# motor_channel_x2.net
KiCad netlist of a schematic drawn in Altium Designer
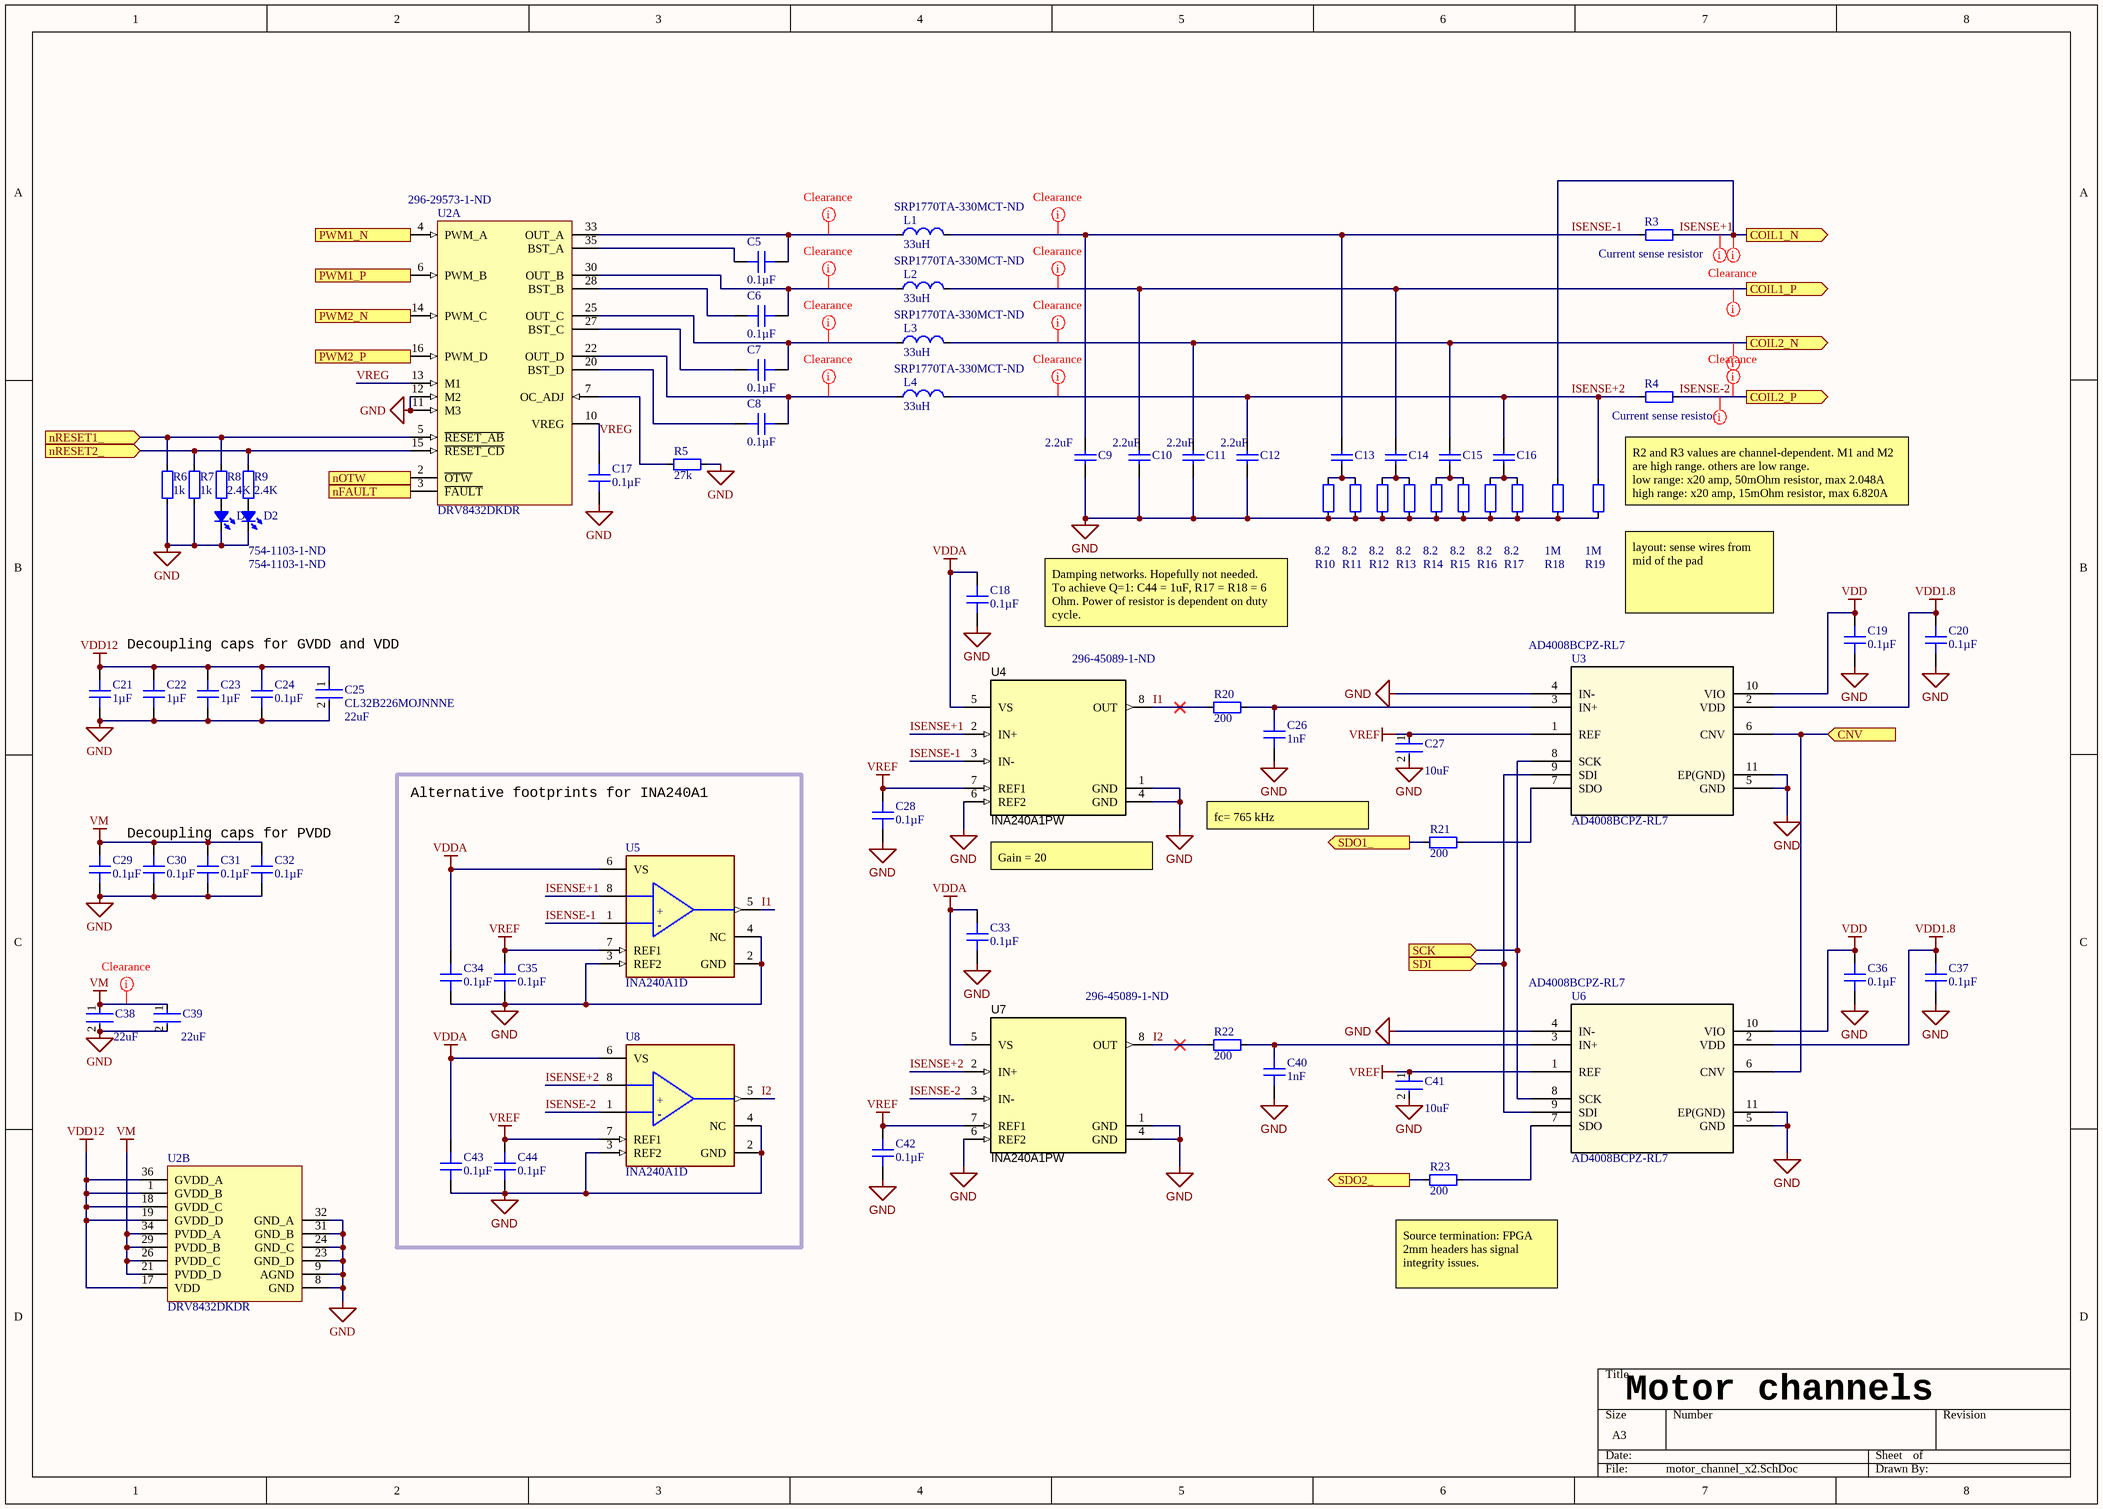
[diagram p0: motor_channel_x2.SchDoc]

(export (version "E")
  (design (tool "Eeschema 10.0.6"))
  (components
    (comp (ref "C5")
      (value "0.1µF")
      (footprint "FP-GRM188-0_1-e0_2_0_55-IPC_B")
      (description "CAP CER 0.1UF 100V X7R 0603")
      (fields (field (name "PART NUMBER") "06031C104KAT2A") (field (name "MANUFACTURER") "AVX Corporation"))
      (libsource (lib "Celestial Altium Library - altium_library") (part "Capacitor"))
    )
    (comp (ref "C6")
      (value "0.1µF")
      (footprint "FP-GRM188-0_1-e0_2_0_55-IPC_B")
      (description "CAP CER 0.1UF 100V X7R 0603")
      (fields (field (name "PART NUMBER") "06031C104KAT2A") (field (name "MANUFACTURER") "AVX Corporation"))
      (libsource (lib "Celestial Altium Library - altium_library") (part "Capacitor"))
    )
    (comp (ref "C7")
      (value "0.1µF")
      (footprint "FP-GRM188-0_1-e0_2_0_55-IPC_B")
      (description "CAP CER 0.1UF 100V X7R 0603")
      (fields (field (name "PART NUMBER") "06031C104KAT2A") (field (name "MANUFACTURER") "AVX Corporation"))
      (libsource (lib "Celestial Altium Library - altium_library") (part "Capacitor"))
    )
    (comp (ref "C8")
      (value "0.1µF")
      (footprint "FP-GRM188-0_1-e0_2_0_55-IPC_B")
      (description "CAP CER 0.1UF 100V X7R 0603")
      (fields (field (name "PART NUMBER") "06031C104KAT2A") (field (name "MANUFACTURER") "AVX Corporation"))
      (libsource (lib "Celestial Altium Library - altium_library") (part "Capacitor"))
    )
    (comp (ref "C9")
      (value "12061C225KAT2A")
      (footprint "CAPC3216X180X50NL20T25")
      (description "Chip Capacitor, 2.2 uF, +/- 10%, 100 V, -55 to 125 degC, 1206 (3216 Metric), RoHS, Tape and Reel")
      (fields
        (field (name "TOLERANCE") "10%")
        (field (name "VOLTAGE") "100V")
        (field (name "CAPACITANCE") "2.2uF")
      )
      (libsource (lib "Altium Content Vault") (part "CAP-NP-2"))
    )
    (comp (ref "C10")
      (value "12061C225KAT2A")
      (footprint "CAPC3216X180X50NL20T25")
      (description "Chip Capacitor, 2.2 uF, +/- 10%, 100 V, -55 to 125 degC, 1206 (3216 Metric), RoHS, Tape and Reel")
      (fields
        (field (name "TOLERANCE") "10%")
        (field (name "VOLTAGE") "100V")
        (field (name "CAPACITANCE") "2.2uF")
      )
      (libsource (lib "Altium Content Vault") (part "CAP-NP-2"))
    )
    (comp (ref "C11")
      (value "12061C225KAT2A")
      (footprint "CAPC3216X180X50NL20T25")
      (description "Chip Capacitor, 2.2 uF, +/- 10%, 100 V, -55 to 125 degC, 1206 (3216 Metric), RoHS, Tape and Reel")
      (fields
        (field (name "TOLERANCE") "10%")
        (field (name "VOLTAGE") "100V")
        (field (name "CAPACITANCE") "2.2uF")
      )
      (libsource (lib "Altium Content Vault") (part "CAP-NP-2"))
    )
    (comp (ref "C12")
      (value "12061C225KAT2A")
      (footprint "CAPC3216X180X50NL20T25")
      (description "Chip Capacitor, 2.2 uF, +/- 10%, 100 V, -55 to 125 degC, 1206 (3216 Metric), RoHS, Tape and Reel")
      (fields
        (field (name "TOLERANCE") "10%")
        (field (name "VOLTAGE") "100V")
        (field (name "CAPACITANCE") "2.2uF")
      )
      (libsource (lib "Altium Content Vault") (part "CAP-NP-2"))
    )
    (comp (ref "C13")
      (value "12061C105KAT2A")
      (footprint "CAPC3216X180X50NL20T25")
      (description "Chip Capacitor, 1 uF, +/- 10%, 100 V, -55 to 125 degC, 1206 (3216 Metric), RoHS, Tape and Reel")
      (fields (field (name "MANUFACTURER") "AVX"))
      (libsource (lib "Altium Content Vault") (part "CAP-NP-2"))
    )
    (comp (ref "C14")
      (value "12061C105KAT2A")
      (footprint "CAPC3216X180X50NL20T25")
      (description "Chip Capacitor, 1 uF, +/- 10%, 100 V, -55 to 125 degC, 1206 (3216 Metric), RoHS, Tape and Reel")
      (fields (field (name "MANUFACTURER") "AVX"))
      (libsource (lib "Altium Content Vault") (part "CAP-NP-2"))
    )
    (comp (ref "C15")
      (value "12061C105KAT2A")
      (footprint "CAPC3216X180X50NL20T25")
      (description "Chip Capacitor, 1 uF, +/- 10%, 100 V, -55 to 125 degC, 1206 (3216 Metric), RoHS, Tape and Reel")
      (fields (field (name "MANUFACTURER") "AVX"))
      (libsource (lib "Altium Content Vault") (part "CAP-NP-2"))
    )
    (comp (ref "C16")
      (value "12061C105KAT2A")
      (footprint "CAPC3216X180X50NL20T25")
      (description "Chip Capacitor, 1 uF, +/- 10%, 100 V, -55 to 125 degC, 1206 (3216 Metric), RoHS, Tape and Reel")
      (fields (field (name "MANUFACTURER") "AVX"))
      (libsource (lib "Altium Content Vault") (part "CAP-NP-2"))
    )
    (comp (ref "C17")
      (value "0.1µF")
      (footprint "FP-GRM155-0_05-IPC_B")
      (description "CAP CER 0.1UF 25V X7R 0402")
      (fields (field (name "PART NUMBER") "04023C104KAT2A") (field (name "MANUFACTURER") "AVX Corporation"))
      (libsource (lib "Celestial Altium Library - altium_library") (part "Capacitor"))
    )
    (comp (ref "C18")
      (value "0.1µF")
      (footprint "FP-GRM155-0_05-IPC_B")
      (description "CAP CER 0.1UF 25V X7R 0402")
      (fields (field (name "MANUFACTURER") "AVX Corporation") (field (name "PART NUMBER") "04023C104KAT2A"))
      (libsource (lib "Celestial Altium Library - altium_library") (part "Capacitor"))
    )
    (comp (ref "C19")
      (value "0.1µF")
      (footprint "FP-GRM155-0_05-IPC_B")
      (description "CAP CER 0.1UF 25V X7R 0402")
      (fields (field (name "MANUFACTURER") "AVX Corporation") (field (name "PART NUMBER") "04023C104KAT2A"))
      (libsource (lib "Celestial Altium Library - altium_library") (part "Capacitor"))
    )
    (comp (ref "C20")
      (value "0.1µF")
      (footprint "FP-GRM155-0_05-IPC_B")
      (description "CAP CER 0.1UF 25V X7R 0402")
      (fields (field (name "MANUFACTURER") "AVX Corporation") (field (name "PART NUMBER") "04023C104KAT2A"))
      (libsource (lib "Celestial Altium Library - altium_library") (part "Capacitor"))
    )
    (comp (ref "C21")
      (value "1µF")
      (footprint "FP-GRM188-0_1-e0_2_0_55-IPC_B")
      (description "CAP CER 1UF 25V X7R 0603")
      (fields (field (name "PART NUMBER") "TMK107B7105KA-T") (field (name "MANUFACTURER") "Taiyo Yuden"))
      (libsource (lib "Celestial Altium Library - altium_library") (part "Capacitor"))
    )
    (comp (ref "C22")
      (value "1µF")
      (footprint "FP-GRM188-0_1-e0_2_0_55-IPC_B")
      (description "CAP CER 1UF 25V X7R 0603")
      (fields (field (name "PART NUMBER") "TMK107B7105KA-T") (field (name "MANUFACTURER") "Taiyo Yuden"))
      (libsource (lib "Celestial Altium Library - altium_library") (part "Capacitor"))
    )
    (comp (ref "C23")
      (value "1µF")
      (footprint "FP-GRM188-0_1-e0_2_0_55-IPC_B")
      (description "CAP CER 1UF 25V X7R 0603")
      (fields (field (name "PART NUMBER") "TMK107B7105KA-T") (field (name "MANUFACTURER") "Taiyo Yuden"))
      (libsource (lib "Celestial Altium Library - altium_library") (part "Capacitor"))
    )
    (comp (ref "C24")
      (value "0.1µF")
      (footprint "FP-GRM155-0_05-IPC_B")
      (description "CAP CER 0.1UF 25V X7R 0402")
      (fields (field (name "MANUFACTURER") "AVX Corporation") (field (name "PART NUMBER") "04023C104KAT2A"))
      (libsource (lib "Celestial Altium Library - altium_library") (part "Capacitor"))
    )
    (comp (ref "C25")
      (value "CL32B226MOJNNNE")
      (footprint "FP-CL32-IPC_B")
      (description "Cap Ceramic 22uF 16V X7R ±20% SMD 1210 +125°C Embossed T/R")
      (fields (field (name "CAPACITANCE") "22uF") (field (name "TOLERANCE") "20%"))
      (libsource (lib "Altium Content Vault") (part "b4654b650e69147ec39a6b967a45e02"))
    )
    (comp (ref "C26")
      (value "1nF")
      (footprint "FP-GRM155-0_05-IPC_B")
      (description "CAP CER 1000PF 25V X7R 0402")
      (fields (field (name "MANUFACTURER") "AVX Corporation") (field (name "PART NUMBER") "04023C102KAT2A"))
      (libsource (lib "Celestial Altium Library - altium_library") (part "Capacitor"))
    )
    (comp (ref "C27")
      (value "CL21B106KQQNNNG")
      (footprint "FP-CL21-IPC_C")
      (description "CL21 Series 0805 10uF 6.3V ±10% Tolerance X7R Multilayer Ceramic Chip Capacitor")
      (fields
        (field (name "CAPACITANCE") "10uF")
        (field (name "TOLERANCE") "10%")
        (field (name "VOLTAGE") "6.3V")
      )
      (libsource (lib "Altium Content Vault") (part "b4654b650e69147ec39a6b967a45e02"))
    )
    (comp (ref "C28")
      (value "0.1µF")
      (footprint "FP-GRM155-0_05-IPC_B")
      (description "CAP CER 0.1UF 25V X7R 0402")
      (fields (field (name "MANUFACTURER") "AVX Corporation") (field (name "PART NUMBER") "04023C104KAT2A"))
      (libsource (lib "Celestial Altium Library - altium_library") (part "Capacitor"))
    )
    (comp (ref "C29")
      (value "0.1µF")
      (footprint "FP-GRM188-0_1-e0_2_0_55-IPC_B")
      (description "CAP CER 0.1UF 100V X7R 0603")
      (fields (field (name "PART NUMBER") "06031C104KAT2A") (field (name "MANUFACTURER") "AVX Corporation"))
      (libsource (lib "Celestial Altium Library - altium_library") (part "Capacitor"))
    )
    (comp (ref "C30")
      (value "0.1µF")
      (footprint "FP-GRM188-0_1-e0_2_0_55-IPC_B")
      (description "CAP CER 0.1UF 100V X7R 0603")
      (fields (field (name "PART NUMBER") "06031C104KAT2A") (field (name "MANUFACTURER") "AVX Corporation"))
      (libsource (lib "Celestial Altium Library - altium_library") (part "Capacitor"))
    )
    (comp (ref "C31")
      (value "0.1µF")
      (footprint "FP-GRM188-0_1-e0_2_0_55-IPC_B")
      (description "CAP CER 0.1UF 100V X7R 0603")
      (fields (field (name "PART NUMBER") "06031C104KAT2A") (field (name "MANUFACTURER") "AVX Corporation"))
      (libsource (lib "Celestial Altium Library - altium_library") (part "Capacitor"))
    )
    (comp (ref "C32")
      (value "0.1µF")
      (footprint "FP-GRM188-0_1-e0_2_0_55-IPC_B")
      (description "CAP CER 0.1UF 100V X7R 0603")
      (fields (field (name "PART NUMBER") "06031C104KAT2A") (field (name "MANUFACTURER") "AVX Corporation"))
      (libsource (lib "Celestial Altium Library - altium_library") (part "Capacitor"))
    )
    (comp (ref "C33")
      (value "0.1µF")
      (footprint "FP-GRM155-0_05-IPC_B")
      (description "CAP CER 0.1UF 25V X7R 0402")
      (fields (field (name "MANUFACTURER") "AVX Corporation") (field (name "PART NUMBER") "04023C104KAT2A"))
      (libsource (lib "Celestial Altium Library - altium_library") (part "Capacitor"))
    )
    (comp (ref "C34")
      (value "0.1µF")
      (footprint "FP-GRM155-0_05-IPC_B")
      (description "CAP CER 0.1UF 25V X7R 0402")
      (fields (field (name "MANUFACTURER") "AVX Corporation") (field (name "PART NUMBER") "04023C104KAT2A"))
      (libsource (lib "Celestial Altium Library - altium_library") (part "Capacitor"))
    )
    (comp (ref "C35")
      (value "0.1µF")
      (footprint "FP-GRM155-0_05-IPC_B")
      (description "CAP CER 0.1UF 25V X7R 0402")
      (fields (field (name "MANUFACTURER") "AVX Corporation") (field (name "PART NUMBER") "04023C104KAT2A"))
      (libsource (lib "Celestial Altium Library - altium_library") (part "Capacitor"))
    )
    (comp (ref "C36")
      (value "0.1µF")
      (footprint "FP-GRM155-0_05-IPC_B")
      (description "CAP CER 0.1UF 25V X7R 0402")
      (fields (field (name "MANUFACTURER") "AVX Corporation") (field (name "PART NUMBER") "04023C104KAT2A"))
      (libsource (lib "Celestial Altium Library - altium_library") (part "Capacitor"))
    )
    (comp (ref "C37")
      (value "0.1µF")
      (footprint "FP-GRM155-0_05-IPC_B")
      (description "CAP CER 0.1UF 25V X7R 0402")
      (fields (field (name "MANUFACTURER") "AVX Corporation") (field (name "PART NUMBER") "04023C104KAT2A"))
      (libsource (lib "Celestial Altium Library - altium_library") (part "Capacitor"))
    )
    (comp (ref "C38")
      (value "KRM55WR72A226MH01L")
      (footprint "FP-KRM55W-6_1_5_3_6_7_1_2-MFG")
      (description "CAP CER 22UF 100V X7R SMD")
      (fields (field (name "CAPACITANCE") "22uF") (field (name "TOLERANCE") "20%"))
      (libsource (lib "Altium Content Vault") (part "02cd4be3c70576c341d710602a673aa"))
    )
    (comp (ref "C39")
      (value "KRM55WR72A226MH01L")
      (footprint "FP-KRM55W-6_1_5_3_6_7_1_2-MFG")
      (description "CAP CER 22UF 100V X7R SMD")
      (fields (field (name "CAPACITANCE") "22uF") (field (name "TOLERANCE") "20%"))
      (libsource (lib "Altium Content Vault") (part "02cd4be3c70576c341d710602a673aa"))
    )
    (comp (ref "C40")
      (value "1nF")
      (footprint "FP-GRM155-0_05-IPC_B")
      (description "CAP CER 1000PF 25V X7R 0402")
      (fields (field (name "MANUFACTURER") "AVX Corporation") (field (name "PART NUMBER") "04023C102KAT2A"))
      (libsource (lib "Celestial Altium Library - altium_library") (part "Capacitor"))
    )
    (comp (ref "C41")
      (value "CL21B106KQQNNNG")
      (footprint "FP-CL21-IPC_C")
      (description "CL21 Series 0805 10uF 6.3V ±10% Tolerance X7R Multilayer Ceramic Chip Capacitor")
      (fields
        (field (name "CAPACITANCE") "10uF")
        (field (name "TOLERANCE") "10%")
        (field (name "VOLTAGE") "6.3V")
      )
      (libsource (lib "Altium Content Vault") (part "b4654b650e69147ec39a6b967a45e02"))
    )
    (comp (ref "C42")
      (value "0.1µF")
      (footprint "FP-GRM155-0_05-IPC_B")
      (description "CAP CER 0.1UF 25V X7R 0402")
      (fields (field (name "MANUFACTURER") "AVX Corporation") (field (name "PART NUMBER") "04023C104KAT2A"))
      (libsource (lib "Celestial Altium Library - altium_library") (part "Capacitor"))
    )
    (comp (ref "C43")
      (value "0.1µF")
      (footprint "FP-GRM155-0_05-IPC_B")
      (description "CAP CER 0.1UF 25V X7R 0402")
      (fields (field (name "MANUFACTURER") "AVX Corporation") (field (name "PART NUMBER") "04023C104KAT2A"))
      (libsource (lib "Celestial Altium Library - altium_library") (part "Capacitor"))
    )
    (comp (ref "C44")
      (value "0.1µF")
      (footprint "FP-GRM155-0_05-IPC_B")
      (description "CAP CER 0.1UF 25V X7R 0402")
      (fields (field (name "MANUFACTURER") "AVX Corporation") (field (name "PART NUMBER") "04023C104KAT2A"))
      (libsource (lib "Celestial Altium Library - altium_library") (part "Capacitor"))
    )
    (comp (ref "D1")
      (value "LED_0402")
      (footprint "Components - 10.02.21 - 05.05:ROHM-SML-P11MT_V")
      (description "LED ORANGE CLEAR CHIP SMD")
      (fields
        (field (name "SUPPLIER PART NUMBER 1") "754-1103-1-ND")
        (field (name "MANUFACTURER") "Kingbright")
        (field (name "MANUFACTURER PART NUMBER") "APHHS1005SECK")
      )
      (libsource (lib "SCH_Active") (part "LED_0402"))
    )
    (comp (ref "D2")
      (value "LED_0402")
      (footprint "Components - 10.02.21 - 05.05:ROHM-SML-P11MT_V")
      (description "LED ORANGE CLEAR CHIP SMD")
      (fields
        (field (name "SUPPLIER PART NUMBER 1") "754-1103-1-ND")
        (field (name "MANUFACTURER") "Kingbright")
        (field (name "MANUFACTURER PART NUMBER") "APHHS1005SECK")
      )
      (libsource (lib "SCH_Active") (part "LED_0402"))
    )
    (comp (ref "L1")
      (value "33uH")
      (footprint "SRP1770TA")
      (fields
        (field (name "MANUFACTURER") "TDK")
        (field (name "MANUFACTURER PART NUMBER") "MPZ2012S300AT000")
        (field (name "TOLERANCE") "20%")
        (field (name "SUPPLIER PART NUMBER 1") "SRP1770TA-330MCT-ND")
      )
      (libsource (lib "SCH_Passive") (part "Ind_0805"))
    )
    (comp (ref "L2")
      (value "33uH")
      (footprint "SRP1770TA")
      (fields
        (field (name "MANUFACTURER") "TDK")
        (field (name "MANUFACTURER PART NUMBER") "MPZ2012S300AT000")
        (field (name "TOLERANCE") "20%")
        (field (name "SUPPLIER PART NUMBER 1") "SRP1770TA-330MCT-ND")
      )
      (libsource (lib "SCH_Passive") (part "Ind_0805"))
    )
    (comp (ref "L3")
      (value "33uH")
      (footprint "SRP1770TA")
      (fields
        (field (name "MANUFACTURER") "TDK")
        (field (name "MANUFACTURER PART NUMBER") "MPZ2012S300AT000")
        (field (name "TOLERANCE") "20%")
        (field (name "SUPPLIER PART NUMBER 1") "SRP1770TA-330MCT-ND")
      )
      (libsource (lib "SCH_Passive") (part "Ind_0805"))
    )
    (comp (ref "L4")
      (value "33uH")
      (footprint "SRP1770TA")
      (fields
        (field (name "MANUFACTURER") "TDK")
        (field (name "MANUFACTURER PART NUMBER") "MPZ2012S300AT000")
        (field (name "TOLERANCE") "20%")
        (field (name "SUPPLIER PART NUMBER 1") "SRP1770TA-330MCT-ND")
      )
      (libsource (lib "SCH_Passive") (part "Ind_0805"))
    )
    (comp (ref "R3")
      (value "Current sense resistor")
      (footprint "STACKPOLE CSR2512")
      (description "RES 2512")
      (libsource (lib "dvrk-s-pwm_2") (part "Res_0402_3"))
    )
    (comp (ref "R4")
      (value "Current sense resistor")
      (footprint "STACKPOLE CSR2512")
      (description "RES 2512")
      (libsource (lib "dvrk-s-pwm_2") (part "Res_0402_3"))
    )
    (comp (ref "R5")
      (value "27k")
      (footprint "FP-CRCW0402-e3-IPC_B")
      (description "Resistor")
      (fields (field (name "Comment") "Res_0402"))
      (libsource (lib "SCH_Passive") (part "Res_0402"))
    )
    (comp (ref "R6")
      (value "1k")
      (footprint "FP-CRCW0805-HPe3-IPC_B")
      (description "Resistor")
      (fields (field (name "Comment") "Res_0805"))
      (libsource (lib "SCH_Passive") (part "Res_0805"))
    )
    (comp (ref "R7")
      (value "1k")
      (footprint "FP-CRCW0805-HPe3-IPC_B")
      (description "Resistor")
      (fields (field (name "Comment") "Res_0805"))
      (libsource (lib "SCH_Passive") (part "Res_0805"))
    )
    (comp (ref "R8")
      (value "2.4K")
      (footprint "FP-CRCW0402-e3-IPC_B")
      (description "Resistor")
      (fields (field (name "Comment") "Res_0402"))
      (libsource (lib "") (part "Res_0402_1"))
    )
    (comp (ref "R9")
      (value "2.4K")
      (footprint "FP-CRCW0402-e3-IPC_B")
      (description "Resistor")
      (fields (field (name "Comment") "Res_0402"))
      (libsource (lib "") (part "Res_0402_1"))
    )
    (comp (ref "R10")
      (value "8.2")
      (footprint "RESC3216X70X50NL05T20")
      (description "Resistor")
      (fields (field (name "Comment") "Res_0402"))
      (libsource (lib "") (part "Res_0402_1"))
    )
    (comp (ref "R11")
      (value "8.2")
      (footprint "RESC3216X70X50NL05T20")
      (description "Resistor")
      (fields (field (name "Comment") "Res_0402"))
      (libsource (lib "") (part "Res_0402_1"))
    )
    (comp (ref "R12")
      (value "8.2")
      (footprint "RESC3216X70X50NL05T20")
      (description "Resistor")
      (fields (field (name "Comment") "Res_0402"))
      (libsource (lib "") (part "Res_0402_1"))
    )
    (comp (ref "R13")
      (value "8.2")
      (footprint "RESC3216X70X50NL05T20")
      (description "Resistor")
      (fields (field (name "Comment") "Res_0402"))
      (libsource (lib "") (part "Res_0402_1"))
    )
    (comp (ref "R14")
      (value "8.2")
      (footprint "RESC3216X70X50NL05T20")
      (description "Resistor")
      (fields (field (name "Comment") "Res_0402"))
      (libsource (lib "") (part "Res_0402_1"))
    )
    (comp (ref "R15")
      (value "8.2")
      (footprint "RESC3216X70X50NL05T20")
      (description "Resistor")
      (fields (field (name "Comment") "Res_0402"))
      (libsource (lib "") (part "Res_0402_1"))
    )
    (comp (ref "R16")
      (value "8.2")
      (footprint "RESC3216X70X50NL05T20")
      (description "Resistor")
      (fields (field (name "Comment") "Res_0402"))
      (libsource (lib "") (part "Res_0402_1"))
    )
    (comp (ref "R17")
      (value "8.2")
      (footprint "RESC3216X70X50NL05T20")
      (description "Resistor")
      (fields (field (name "Comment") "Res_0402"))
      (libsource (lib "") (part "Res_0402_1"))
    )
    (comp (ref "R18")
      (value "1M")
      (footprint "FP-CRCW0402-e3-IPC_B")
      (description "Resistor")
      (fields (field (name "Comment") "Res_0402"))
      (libsource (lib "") (part "Res_0402_1"))
    )
    (comp (ref "R19")
      (value "1M")
      (footprint "FP-CRCW0402-e3-IPC_B")
      (description "Resistor")
      (fields (field (name "Comment") "Res_0402"))
      (libsource (lib "") (part "Res_0402_1"))
    )
    (comp (ref "R20")
      (value "200")
      (footprint "FP-CRCW0402-e3-IPC_B")
      (description "Resistor")
      (fields (field (name "Comment") "Res_0402"))
      (libsource (lib "SCH_Passive") (part "Res_0402"))
    )
    (comp (ref "R21")
      (value "200")
      (footprint "FP-CRCW0402-e3-IPC_B")
      (description "Resistor")
      (fields (field (name "Comment") "Res_0402"))
      (libsource (lib "SCH_Passive") (part "Res_0402"))
    )
    (comp (ref "R22")
      (value "200")
      (footprint "FP-CRCW0402-e3-IPC_B")
      (description "Resistor")
      (fields (field (name "Comment") "Res_0402"))
      (libsource (lib "SCH_Passive") (part "Res_0402"))
    )
    (comp (ref "R23")
      (value "200")
      (footprint "FP-CRCW0402-e3-IPC_B")
      (description "Resistor")
      (fields (field (name "Comment") "Res_0402"))
      (libsource (lib "SCH_Passive") (part "Res_0402"))
    )
    (comp (ref "U2")
      (value "DRV8432DKDR")
      (footprint "DKD0036A_L_extra_clearance")
      (fields
        (field (name "SUPPLIER PART NUMBER 1") "296-29573-1-ND")
        (field (name "MANUFACTURER") "Texas Instruments")
      )
      (libsource (lib "dvrk-s-pwm_2") (part "TI-DRV8432DKD36"))
    )
    (comp (ref "U3")
      (value "AD4008BCPZ-RL7")
      (footprint "CP_10_9")
      (description "16-Bit, 2 MSPS/1 MSPS/500 kSPS,\r\nPrecision, Pseudo Differential, SAR ADCs")
      (fields (field (name "SUPPLIER PART NUMBER 1") "AD4008BCPZ-RL7"))
      (libsource (lib "dvrk-s-pwm") (part "AD4008BCPZ-RL7"))
    )
    (comp (ref "U4")
      (value "INA240A1PW")
      (footprint "drac_v31:PW0008A_N")
      (description "TEXAS INSTRUMENTS - INA240A1PWR . - CURRENT SENSE AMPLIFIER, 400KHZ, TSSOP-8")
      (fields
        (field (name "MANUFACTURER") "Texas Instruments")
        (field (name "MANUFACTURER PART NUMBER") "INA240A1PWR")
        (field (name "SUPPLIER PART NUMBER 1") "296-45089-1-ND")
        (field (name "SYMBOLCREATOR") "Altium")
        (field (name "PUBLISHER") "Texas Instruments")
      )
      (libsource (lib "TI_Pre_RTM") (part "INA240A1PW"))
    )
    (comp (ref "U5")
      (value "INA240A1D")
      (footprint "drac_v31:FP-D0008A-IPC_C")
      (description "IC CURR SENSE 1 CIRCUIT 8SOIC")
      (libsource (lib "dvrk-s-pwm_2") (part "9e341c39a96748c47c80be35c7bc850"))
    )
    (comp (ref "U6")
      (value "AD4008BCPZ-RL7")
      (footprint "CP_10_9")
      (description "16-Bit, 2 MSPS/1 MSPS/500 kSPS,\r\nPrecision, Pseudo Differential, SAR ADCs")
      (fields (field (name "SUPPLIER PART NUMBER 1") "AD4008BCPZ-RL7"))
      (libsource (lib "dvrk-s-pwm") (part "AD4008BCPZ-RL7"))
    )
    (comp (ref "U7")
      (value "INA240A1PW")
      (footprint "drac_v31:PW0008A_N")
      (description "TEXAS INSTRUMENTS - INA240A1PWR . - CURRENT SENSE AMPLIFIER, 400KHZ, TSSOP-8")
      (fields
        (field (name "MANUFACTURER") "Texas Instruments")
        (field (name "MANUFACTURER PART NUMBER") "INA240A1PWR")
        (field (name "SUPPLIER PART NUMBER 1") "296-45089-1-ND")
        (field (name "SYMBOLCREATOR") "Altium")
        (field (name "PUBLISHER") "Texas Instruments")
      )
      (libsource (lib "TI_Pre_RTM") (part "INA240A1PW"))
    )
    (comp (ref "U8")
      (value "INA240A1D")
      (footprint "drac_v31:FP-D0008A-IPC_C")
      (description "IC CURR SENSE 1 CIRCUIT 8SOIC")
      (libsource (lib "dvrk-s-pwm_2") (part "9e341c39a96748c47c80be35c7bc850"))
    )
  )
  (nets
    (net (code "1") (name "/CNV") (class "Default")
      (node (ref "U3") (pin "6") (pinfunction "CNV_6") (pintype "passive"))
      (node (ref "U6") (pin "6") (pinfunction "CNV_6") (pintype "passive"))
    )
    (net (code "2") (name "/COIL1_P") (class "Default")
      (node (ref "C10") (pin "2") (pinfunction "2_2") (pintype "passive"))
      (node (ref "C14") (pin "1") (pinfunction "1_1") (pintype "passive"))
      (node (ref "L2") (pin "2") (pinfunction "2_2") (pintype "passive"))
    )
    (net (code "3") (name "/COIL2_N") (class "Default")
      (node (ref "C11") (pin "2") (pinfunction "2_2") (pintype "passive"))
      (node (ref "C15") (pin "1") (pinfunction "1_1") (pintype "passive"))
      (node (ref "L3") (pin "2") (pinfunction "2_2") (pintype "passive"))
    )
    (net (code "4") (name "/I1") (class "Default")
      (node (ref "R20") (pin "1") (pinfunction "1_1") (pintype "passive"))
      (node (ref "U4") (pin "8") (pinfunction "OUT_8") (pintype "output"))
      (node (ref "U5") (pin "5") (pinfunction "OUT_5") (pintype "output"))
    )
    (net (code "5") (name "/I2") (class "Default")
      (node (ref "R22") (pin "1") (pinfunction "1_1") (pintype "passive"))
      (node (ref "U7") (pin "8") (pinfunction "OUT_8") (pintype "output"))
      (node (ref "U8") (pin "5") (pinfunction "OUT_5") (pintype "output"))
    )
    (net (code "6") (name "/ISENSE+1") (class "Default")
      (node (ref "R18") (pin "2") (pinfunction "2_2") (pintype "passive"))
      (node (ref "R3") (pin "2") (pinfunction "2_2") (pintype "passive"))
      (node (ref "U4") (pin "2") (pinfunction "IN+_2") (pintype "input"))
      (node (ref "U5") (pin "8") (pinfunction "IN+_8") (pintype "tri_state"))
    )
    (net (code "7") (name "/ISENSE+2") (class "Default")
      (node (ref "C12") (pin "2") (pinfunction "2_2") (pintype "passive"))
      (node (ref "C16") (pin "1") (pinfunction "1_1") (pintype "passive"))
      (node (ref "L4") (pin "2") (pinfunction "2_2") (pintype "passive"))
      (node (ref "R19") (pin "2") (pinfunction "2_2") (pintype "passive"))
      (node (ref "R4") (pin "1") (pinfunction "1_1") (pintype "passive"))
      (node (ref "U7") (pin "2") (pinfunction "IN+_2") (pintype "input"))
      (node (ref "U8") (pin "8") (pinfunction "IN+_8") (pintype "tri_state"))
    )
    (net (code "8") (name "/ISENSE-1") (class "Default")
      (node (ref "C13") (pin "1") (pinfunction "1_1") (pintype "passive"))
      (node (ref "C9") (pin "2") (pinfunction "2_2") (pintype "passive"))
      (node (ref "L1") (pin "2") (pinfunction "2_2") (pintype "passive"))
      (node (ref "R3") (pin "1") (pinfunction "1_1") (pintype "passive"))
      (node (ref "U4") (pin "3") (pinfunction "IN-_3") (pintype "input"))
      (node (ref "U5") (pin "1") (pinfunction "IN-_1") (pintype "tri_state"))
    )
    (net (code "9") (name "/ISENSE-2") (class "Default")
      (node (ref "R4") (pin "2") (pinfunction "2_2") (pintype "passive"))
      (node (ref "U7") (pin "3") (pinfunction "IN-_3") (pintype "input"))
      (node (ref "U8") (pin "1") (pinfunction "IN-_1") (pintype "tri_state"))
    )
    (net (code "10") (name "/PWM1_N") (class "Default")
      (node (ref "U2") (pin "4") (pinfunction "PWM_A_4") (pintype "input"))
    )
    (net (code "11") (name "/PWM1_P") (class "Default")
      (node (ref "U2") (pin "6") (pinfunction "PWM_B_6") (pintype "input"))
    )
    (net (code "12") (name "/PWM2_N") (class "Default")
      (node (ref "U2") (pin "14") (pinfunction "PWM_C_14") (pintype "input"))
    )
    (net (code "13") (name "/PWM2_P") (class "Default")
      (node (ref "U2") (pin "16") (pinfunction "PWM_D_16") (pintype "input"))
    )
    (net (code "14") (name "/SCK") (class "Default")
      (node (ref "U3") (pin "8") (pinfunction "SCK_8") (pintype "passive"))
      (node (ref "U6") (pin "8") (pinfunction "SCK_8") (pintype "passive"))
    )
    (net (code "15") (name "/SDI") (class "Default")
      (node (ref "U3") (pin "9") (pinfunction "SDI_9") (pintype "passive"))
      (node (ref "U6") (pin "9") (pinfunction "SDI_9") (pintype "passive"))
    )
    (net (code "16") (name "/SDO1_") (class "Default")
      (node (ref "R21") (pin "1") (pinfunction "1_1") (pintype "passive"))
    )
    (net (code "17") (name "/SDO2_") (class "Default")
      (node (ref "R23") (pin "1") (pinfunction "1_1") (pintype "passive"))
    )
    (net (code "18") (name "/VREG") (class "Default")
      (node (ref "C17") (pin "1") (pinfunction "1_1") (pintype "passive"))
      (node (ref "U2") (pin "10") (pinfunction "VREG_10") (pintype "passive"))
      (node (ref "U2") (pin "13") (pinfunction "M1_13") (pintype "input"))
    )
    (net (code "19") (name "/nFAULT") (class "Default")
      (node (ref "U2") (pin "3") (pinfunction "~{FAULT}_3") (pintype "open_collector"))
    )
    (net (code "20") (name "/nOTW") (class "Default")
      (node (ref "U2") (pin "2") (pinfunction "~{OTW}_2") (pintype "open_collector"))
    )
    (net (code "21") (name "/nRESET1_") (class "Default")
      (node (ref "R6") (pin "2") (pinfunction "2_2") (pintype "passive"))
      (node (ref "R8") (pin "2") (pinfunction "2_2") (pintype "passive"))
      (node (ref "U2") (pin "5") (pinfunction "~{RESET_AB}_5") (pintype "input"))
    )
    (net (code "22") (name "/nRESET2_") (class "Default")
      (node (ref "R7") (pin "2") (pinfunction "2_2") (pintype "passive"))
      (node (ref "R9") (pin "2") (pinfunction "2_2") (pintype "passive"))
      (node (ref "U2") (pin "15") (pinfunction "~{RESET_CD}_15") (pintype "input"))
    )
    (net (code "23") (name "GND") (class "Default")
      (node (ref "C10") (pin "1") (pinfunction "1_1") (pintype "passive"))
      (node (ref "C11") (pin "1") (pinfunction "1_1") (pintype "passive"))
      (node (ref "C12") (pin "1") (pinfunction "1_1") (pintype "passive"))
      (node (ref "C17") (pin "2") (pinfunction "2_2") (pintype "passive"))
      (node (ref "C18") (pin "2") (pinfunction "2_2") (pintype "passive"))
      (node (ref "C19") (pin "2") (pinfunction "2_2") (pintype "passive"))
      (node (ref "C20") (pin "2") (pinfunction "2_2") (pintype "passive"))
      (node (ref "C21") (pin "2") (pinfunction "2_2") (pintype "passive"))
      (node (ref "C22") (pin "2") (pinfunction "2_2") (pintype "passive"))
      (node (ref "C23") (pin "2") (pinfunction "2_2") (pintype "passive"))
      (node (ref "C24") (pin "2") (pinfunction "2_2") (pintype "passive"))
      (node (ref "C25") (pin "2") (pinfunction "2_2") (pintype "passive"))
      (node (ref "C26") (pin "2") (pinfunction "2_2") (pintype "passive"))
      (node (ref "C27") (pin "2") (pinfunction "2_2") (pintype "passive"))
      (node (ref "C28") (pin "2") (pinfunction "2_2") (pintype "passive"))
      (node (ref "C29") (pin "2") (pinfunction "2_2") (pintype "passive"))
      (node (ref "C30") (pin "2") (pinfunction "2_2") (pintype "passive"))
      (node (ref "C31") (pin "2") (pinfunction "2_2") (pintype "passive"))
      (node (ref "C32") (pin "2") (pinfunction "2_2") (pintype "passive"))
      (node (ref "C33") (pin "2") (pinfunction "2_2") (pintype "passive"))
      (node (ref "C34") (pin "2") (pinfunction "2_2") (pintype "passive"))
      (node (ref "C35") (pin "2") (pinfunction "2_2") (pintype "passive"))
      (node (ref "C36") (pin "2") (pinfunction "2_2") (pintype "passive"))
      (node (ref "C37") (pin "2") (pinfunction "2_2") (pintype "passive"))
      (node (ref "C38") (pin "2") (pinfunction "2_2") (pintype "passive"))
      (node (ref "C39") (pin "2") (pinfunction "2_2") (pintype "passive"))
      (node (ref "C40") (pin "2") (pinfunction "2_2") (pintype "passive"))
      (node (ref "C41") (pin "2") (pinfunction "2_2") (pintype "passive"))
      (node (ref "C42") (pin "2") (pinfunction "2_2") (pintype "passive"))
      (node (ref "C43") (pin "2") (pinfunction "2_2") (pintype "passive"))
      (node (ref "C44") (pin "2") (pinfunction "2_2") (pintype "passive"))
      (node (ref "C9") (pin "1") (pinfunction "1_1") (pintype "passive"))
      (node (ref "D1") (pin "2") (pinfunction "K_2") (pintype "passive"))
      (node (ref "D2") (pin "2") (pinfunction "K_2") (pintype "passive"))
      (node (ref "R10") (pin "1") (pinfunction "1_1") (pintype "passive"))
      (node (ref "R11") (pin "1") (pinfunction "1_1") (pintype "passive"))
      (node (ref "R12") (pin "1") (pinfunction "1_1") (pintype "passive"))
      (node (ref "R13") (pin "1") (pinfunction "1_1") (pintype "passive"))
      (node (ref "R14") (pin "1") (pinfunction "1_1") (pintype "passive"))
      (node (ref "R15") (pin "1") (pinfunction "1_1") (pintype "passive"))
      (node (ref "R16") (pin "1") (pinfunction "1_1") (pintype "passive"))
      (node (ref "R17") (pin "1") (pinfunction "1_1") (pintype "passive"))
      (node (ref "R18") (pin "1") (pinfunction "1_1") (pintype "passive"))
      (node (ref "R19") (pin "1") (pinfunction "1_1") (pintype "passive"))
      (node (ref "R5") (pin "2") (pinfunction "2_2") (pintype "passive"))
      (node (ref "R6") (pin "1") (pinfunction "1_1") (pintype "passive"))
      (node (ref "R7") (pin "1") (pinfunction "1_1") (pintype "passive"))
      (node (ref "U2") (pin "11") (pinfunction "M3_11") (pintype "input"))
      (node (ref "U2") (pin "12") (pinfunction "M2_12") (pintype "input"))
      (node (ref "U2") (pin "23") (pinfunction "GND_D_23") (pintype "power_in"))
      (node (ref "U2") (pin "24") (pinfunction "GND_C_24") (pintype "power_in"))
      (node (ref "U2") (pin "31") (pinfunction "GND_B_31") (pintype "power_in"))
      (node (ref "U2") (pin "32") (pinfunction "GND_A_32") (pintype "power_in"))
      (node (ref "U2") (pin "8") (pinfunction "GND_8") (pintype "power_in"))
      (node (ref "U2") (pin "9") (pinfunction "AGND_9") (pintype "power_in"))
      (node (ref "U3") (pin "11") (pinfunction "EP(GND)_11") (pintype "passive"))
      (node (ref "U3") (pin "4") (pinfunction "IN-_4") (pintype "passive"))
      (node (ref "U3") (pin "5") (pinfunction "GND_5") (pintype "passive"))
      (node (ref "U4") (pin "1") (pinfunction "GND_1") (pintype "power_in"))
      (node (ref "U4") (pin "4") (pinfunction "GND_4") (pintype "power_in"))
      (node (ref "U4") (pin "6") (pinfunction "REF2_6") (pintype "input"))
      (node (ref "U5") (pin "2") (pinfunction "GND_2") (pintype "power_in"))
      (node (ref "U5") (pin "3") (pinfunction "REF2_3") (pintype "input"))
      (node (ref "U5") (pin "4") (pinfunction "NC_4") (pintype "passive"))
      (node (ref "U6") (pin "11") (pinfunction "EP(GND)_11") (pintype "passive"))
      (node (ref "U6") (pin "4") (pinfunction "IN-_4") (pintype "passive"))
      (node (ref "U6") (pin "5") (pinfunction "GND_5") (pintype "passive"))
      (node (ref "U7") (pin "1") (pinfunction "GND_1") (pintype "power_in"))
      (node (ref "U7") (pin "4") (pinfunction "GND_4") (pintype "power_in"))
      (node (ref "U7") (pin "6") (pinfunction "REF2_6") (pintype "input"))
      (node (ref "U8") (pin "2") (pinfunction "GND_2") (pintype "power_in"))
      (node (ref "U8") (pin "3") (pinfunction "REF2_3") (pintype "input"))
      (node (ref "U8") (pin "4") (pinfunction "NC_4") (pintype "passive"))
    )
    (net (code "24") (name "Net-(C13-Pad2)") (class "Default")
      (node (ref "C13") (pin "2") (pinfunction "2_2") (pintype "passive"))
      (node (ref "R10") (pin "2") (pinfunction "2_2") (pintype "passive"))
      (node (ref "R11") (pin "2") (pinfunction "2_2") (pintype "passive"))
    )
    (net (code "25") (name "Net-(C14-Pad2)") (class "Default")
      (node (ref "C14") (pin "2") (pinfunction "2_2") (pintype "passive"))
      (node (ref "R12") (pin "2") (pinfunction "2_2") (pintype "passive"))
      (node (ref "R13") (pin "2") (pinfunction "2_2") (pintype "passive"))
    )
    (net (code "26") (name "Net-(C15-Pad2)") (class "Default")
      (node (ref "C15") (pin "2") (pinfunction "2_2") (pintype "passive"))
      (node (ref "R14") (pin "2") (pinfunction "2_2") (pintype "passive"))
      (node (ref "R15") (pin "2") (pinfunction "2_2") (pintype "passive"))
    )
    (net (code "27") (name "Net-(C16-Pad2)") (class "Default")
      (node (ref "C16") (pin "2") (pinfunction "2_2") (pintype "passive"))
      (node (ref "R16") (pin "2") (pinfunction "2_2") (pintype "passive"))
      (node (ref "R17") (pin "2") (pinfunction "2_2") (pintype "passive"))
    )
    (net (code "28") (name "Net-(D1-A)") (class "Default")
      (node (ref "D1") (pin "1") (pinfunction "A_1") (pintype "passive"))
      (node (ref "R8") (pin "1") (pinfunction "1_1") (pintype "passive"))
    )
    (net (code "29") (name "Net-(D2-A)") (class "Default")
      (node (ref "D2") (pin "1") (pinfunction "A_1") (pintype "passive"))
      (node (ref "R9") (pin "1") (pinfunction "1_1") (pintype "passive"))
    )
    (net (code "30") (name "Net-(U2A-BST_A)") (class "Default")
      (node (ref "C5") (pin "1") (pinfunction "1_1") (pintype "passive"))
      (node (ref "U2") (pin "35") (pinfunction "BST_A_35") (pintype "passive"))
    )
    (net (code "31") (name "Net-(U2A-BST_B)") (class "Default")
      (node (ref "C6") (pin "1") (pinfunction "1_1") (pintype "passive"))
      (node (ref "U2") (pin "28") (pinfunction "BST_B_28") (pintype "passive"))
    )
    (net (code "32") (name "Net-(U2A-BST_C)") (class "Default")
      (node (ref "C7") (pin "1") (pinfunction "1_1") (pintype "passive"))
      (node (ref "U2") (pin "27") (pinfunction "BST_C_27") (pintype "passive"))
    )
    (net (code "33") (name "Net-(U2A-BST_D)") (class "Default")
      (node (ref "C8") (pin "1") (pinfunction "1_1") (pintype "passive"))
      (node (ref "U2") (pin "20") (pinfunction "BST_D_20") (pintype "passive"))
    )
    (net (code "34") (name "Net-(U2A-OC_ADJ)") (class "Default")
      (node (ref "R5") (pin "1") (pinfunction "1_1") (pintype "passive"))
      (node (ref "U2") (pin "7") (pinfunction "OC_ADJ_7") (pintype "input"))
    )
    (net (code "35") (name "Net-(U2A-OUT_A)") (class "Default")
      (node (ref "C5") (pin "2") (pinfunction "2_2") (pintype "passive"))
      (node (ref "L1") (pin "1") (pinfunction "1_1") (pintype "passive"))
      (node (ref "U2") (pin "33") (pinfunction "OUT_A_33") (pintype "tri_state"))
    )
    (net (code "36") (name "Net-(U2A-OUT_B)") (class "Default")
      (node (ref "C6") (pin "2") (pinfunction "2_2") (pintype "passive"))
      (node (ref "L2") (pin "1") (pinfunction "1_1") (pintype "passive"))
      (node (ref "U2") (pin "30") (pinfunction "OUT_B_30") (pintype "tri_state"))
    )
    (net (code "37") (name "Net-(U2A-OUT_C)") (class "Default")
      (node (ref "C7") (pin "2") (pinfunction "2_2") (pintype "passive"))
      (node (ref "L3") (pin "1") (pinfunction "1_1") (pintype "passive"))
      (node (ref "U2") (pin "25") (pinfunction "OUT_C_25") (pintype "tri_state"))
    )
    (net (code "38") (name "Net-(U2A-OUT_D)") (class "Default")
      (node (ref "C8") (pin "2") (pinfunction "2_2") (pintype "passive"))
      (node (ref "L4") (pin "1") (pinfunction "1_1") (pintype "passive"))
      (node (ref "U2") (pin "22") (pinfunction "OUT_D_22") (pintype "tri_state"))
    )
    (net (code "39") (name "Net-(U3-IN+)") (class "Default")
      (node (ref "C26") (pin "1") (pinfunction "1_1") (pintype "passive"))
      (node (ref "R20") (pin "2") (pinfunction "2_2") (pintype "passive"))
      (node (ref "U3") (pin "3") (pinfunction "IN+_3") (pintype "passive"))
    )
    (net (code "40") (name "Net-(U3-SDO)") (class "Default")
      (node (ref "R21") (pin "2") (pinfunction "2_2") (pintype "passive"))
      (node (ref "U3") (pin "7") (pinfunction "SDO_7") (pintype "passive"))
    )
    (net (code "41") (name "Net-(U6-IN+)") (class "Default")
      (node (ref "C40") (pin "1") (pinfunction "1_1") (pintype "passive"))
      (node (ref "R22") (pin "2") (pinfunction "2_2") (pintype "passive"))
      (node (ref "U6") (pin "3") (pinfunction "IN+_3") (pintype "passive"))
    )
    (net (code "42") (name "Net-(U6-SDO)") (class "Default")
      (node (ref "R23") (pin "2") (pinfunction "2_2") (pintype "passive"))
      (node (ref "U6") (pin "7") (pinfunction "SDO_7") (pintype "passive"))
    )
    (net (code "43") (name "VDD") (class "Default")
      (node (ref "C19") (pin "1") (pinfunction "1_1") (pintype "passive"))
      (node (ref "C36") (pin "1") (pinfunction "1_1") (pintype "passive"))
      (node (ref "U3") (pin "10") (pinfunction "VIO_10") (pintype "passive"))
      (node (ref "U6") (pin "10") (pinfunction "VIO_10") (pintype "passive"))
    )
    (net (code "44") (name "VDD1.8") (class "Default")
      (node (ref "C20") (pin "1") (pinfunction "1_1") (pintype "passive"))
      (node (ref "C37") (pin "1") (pinfunction "1_1") (pintype "passive"))
      (node (ref "U3") (pin "2") (pinfunction "VDD_2") (pintype "passive"))
      (node (ref "U6") (pin "2") (pinfunction "VDD_2") (pintype "passive"))
    )
    (net (code "45") (name "VDD12") (class "Default")
      (node (ref "C21") (pin "1") (pinfunction "1_1") (pintype "passive"))
      (node (ref "C22") (pin "1") (pinfunction "1_1") (pintype "passive"))
      (node (ref "C23") (pin "1") (pinfunction "1_1") (pintype "passive"))
      (node (ref "C24") (pin "1") (pinfunction "1_1") (pintype "passive"))
      (node (ref "C25") (pin "1") (pinfunction "1_1") (pintype "passive"))
      (node (ref "U2") (pin "1") (pinfunction "GVDD_B_1") (pintype "power_in"))
      (node (ref "U2") (pin "17") (pinfunction "VDD_17") (pintype "power_in"))
      (node (ref "U2") (pin "18") (pinfunction "GVDD_C_18") (pintype "power_in"))
      (node (ref "U2") (pin "19") (pinfunction "GVDD_D_19") (pintype "power_in"))
      (node (ref "U2") (pin "36") (pinfunction "GVDD_A_36") (pintype "power_in"))
    )
    (net (code "46") (name "VDDA") (class "Default")
      (node (ref "C18") (pin "1") (pinfunction "1_1") (pintype "passive"))
      (node (ref "C33") (pin "1") (pinfunction "1_1") (pintype "passive"))
      (node (ref "C34") (pin "1") (pinfunction "1_1") (pintype "passive"))
      (node (ref "C43") (pin "1") (pinfunction "1_1") (pintype "passive"))
      (node (ref "U4") (pin "5") (pinfunction "VS_5") (pintype "power_in"))
      (node (ref "U5") (pin "6") (pinfunction "VS_6") (pintype "power_in"))
      (node (ref "U7") (pin "5") (pinfunction "VS_5") (pintype "power_in"))
      (node (ref "U8") (pin "6") (pinfunction "VS_6") (pintype "power_in"))
    )
    (net (code "47") (name "VM") (class "Default")
      (node (ref "C29") (pin "1") (pinfunction "1_1") (pintype "passive"))
      (node (ref "C30") (pin "1") (pinfunction "1_1") (pintype "passive"))
      (node (ref "C31") (pin "1") (pinfunction "1_1") (pintype "passive"))
      (node (ref "C32") (pin "1") (pinfunction "1_1") (pintype "passive"))
      (node (ref "C38") (pin "1") (pinfunction "1_1") (pintype "passive"))
      (node (ref "C39") (pin "1") (pinfunction "1_1") (pintype "passive"))
      (node (ref "U2") (pin "21") (pinfunction "PVDD_D_21") (pintype "power_in"))
      (node (ref "U2") (pin "26") (pinfunction "PVDD_C_26") (pintype "power_in"))
      (node (ref "U2") (pin "29") (pinfunction "PVDD_B_29") (pintype "power_in"))
      (node (ref "U2") (pin "34") (pinfunction "PVDD_A_34") (pintype "power_in"))
    )
    (net (code "48") (name "VREF") (class "Default")
      (node (ref "C27") (pin "1") (pinfunction "1_1") (pintype "passive"))
      (node (ref "C28") (pin "1") (pinfunction "1_1") (pintype "passive"))
      (node (ref "C35") (pin "1") (pinfunction "1_1") (pintype "passive"))
      (node (ref "C41") (pin "1") (pinfunction "1_1") (pintype "passive"))
      (node (ref "C42") (pin "1") (pinfunction "1_1") (pintype "passive"))
      (node (ref "C44") (pin "1") (pinfunction "1_1") (pintype "passive"))
      (node (ref "U3") (pin "1") (pinfunction "REF_1") (pintype "passive"))
      (node (ref "U4") (pin "7") (pinfunction "REF1_7") (pintype "input"))
      (node (ref "U5") (pin "7") (pinfunction "REF1_7") (pintype "input"))
      (node (ref "U6") (pin "1") (pinfunction "REF_1") (pintype "passive"))
      (node (ref "U7") (pin "7") (pinfunction "REF1_7") (pintype "input"))
      (node (ref "U8") (pin "7") (pinfunction "REF1_7") (pintype "input"))
    )
  )
)
